# ethernet.net
KiCad netlist of a schematic drawn in Altium Designer
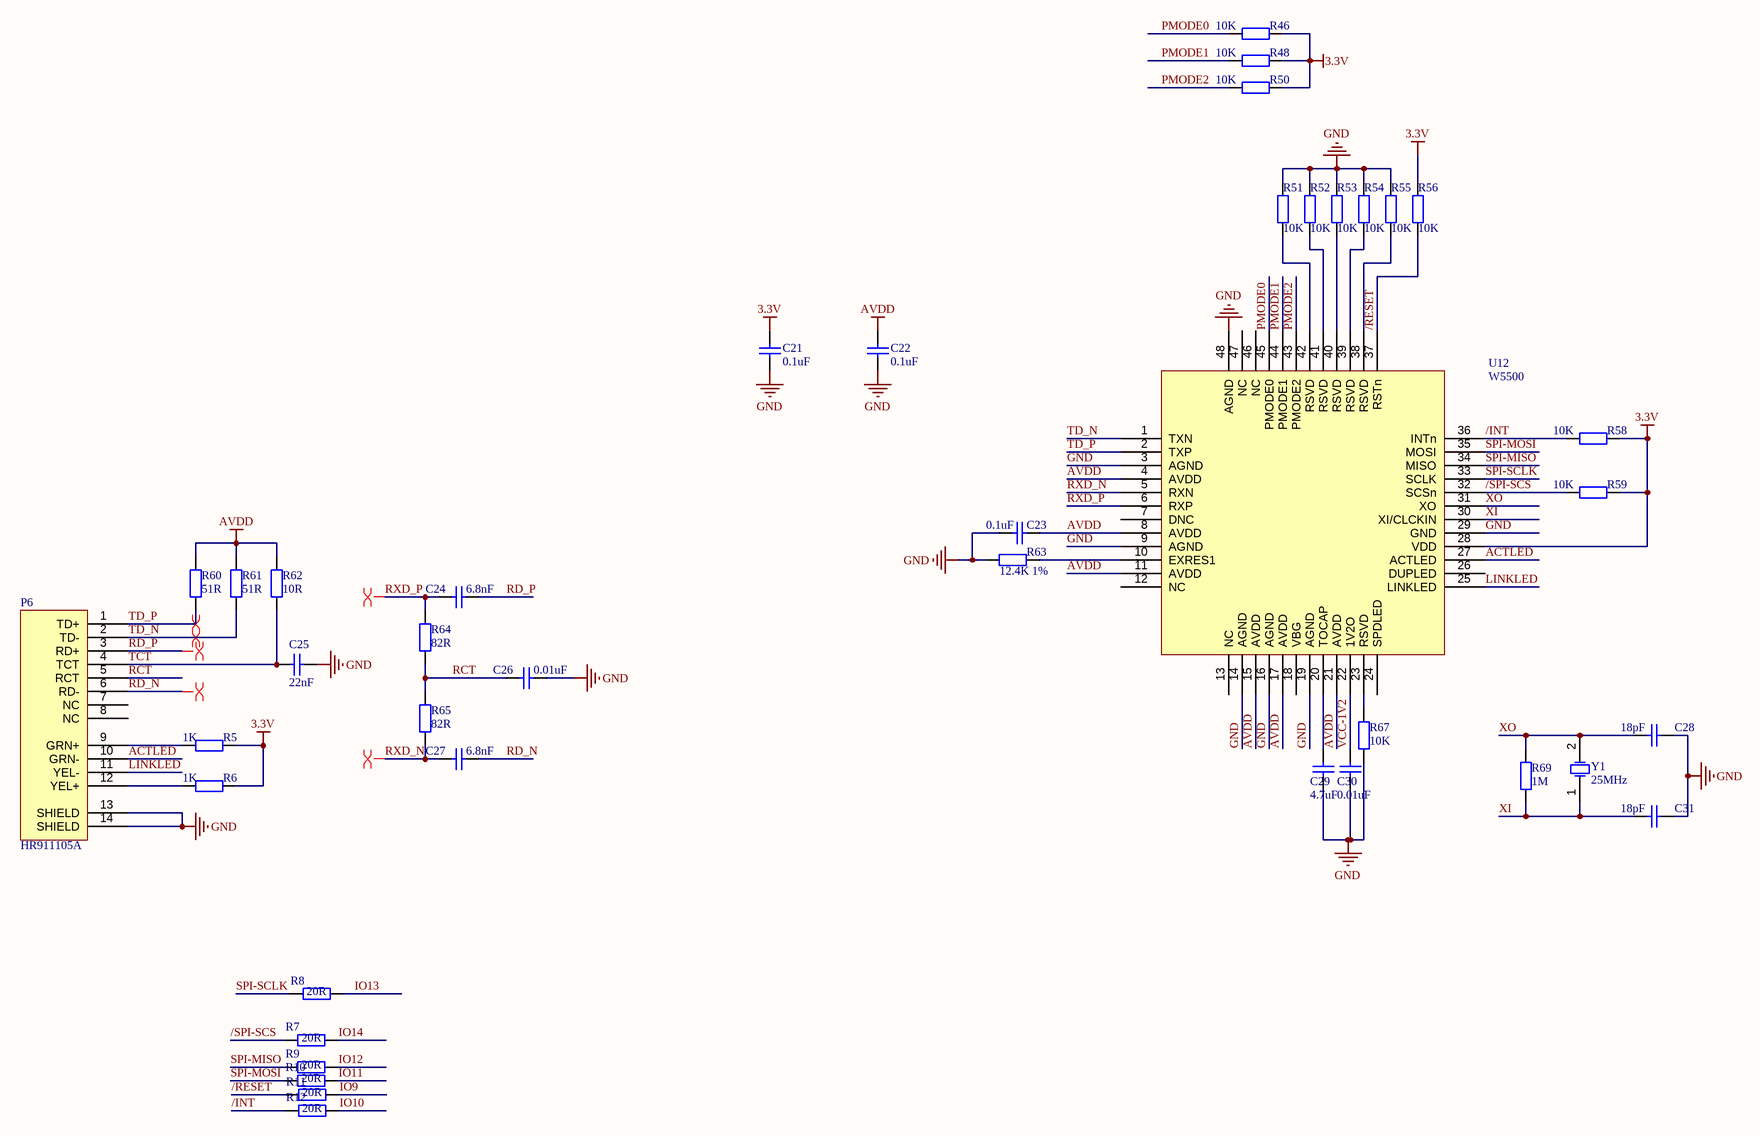
[diagram p0: ethernet.SchDoc]

(export (version "E")
  (design (tool "Eeschema 10.0.6"))
  (components
    (comp (ref "C21")
      (value "0.1uF")
      (footprint "C0805")
      (description "Capacitor")
      (fields (field (name "Comment") "Cap") (field (name "PUBLISHER") "Altium Limited"))
      (libsource (lib "Miscellaneous Devices") (part "Cap"))
    )
    (comp (ref "C22")
      (value "0.1uF")
      (footprint "C0805")
      (description "Capacitor")
      (fields (field (name "Comment") "Cap") (field (name "PUBLISHER") "Altium Limited"))
      (libsource (lib "Miscellaneous Devices") (part "Cap"))
    )
    (comp (ref "C23")
      (value "0.1uF")
      (footprint "C0805")
      (description "Capacitor")
      (fields (field (name "Comment") "Cap") (field (name "PUBLISHER") "Altium Limited"))
      (libsource (lib "Miscellaneous Devices") (part "Cap"))
    )
    (comp (ref "C24")
      (value "6.8nF")
      (footprint "C0805")
      (description "Capacitor")
      (fields (field (name "Comment") "Cap") (field (name "PUBLISHER") "Altium Limited"))
      (libsource (lib "Miscellaneous Devices") (part "Cap"))
    )
    (comp (ref "C25")
      (value "22nF")
      (footprint "C0805")
      (description "Capacitor")
      (fields (field (name "Comment") "Cap") (field (name "PUBLISHER") "Altium Limited"))
      (libsource (lib "Miscellaneous Devices") (part "Cap"))
    )
    (comp (ref "C26")
      (value "0.01uF")
      (footprint "C0805")
      (description "Capacitor")
      (fields (field (name "Comment") "Cap") (field (name "PUBLISHER") "Altium Limited"))
      (libsource (lib "Miscellaneous Devices") (part "Cap"))
    )
    (comp (ref "C27")
      (value "6.8nF")
      (footprint "C0805")
      (description "Capacitor")
      (fields (field (name "Comment") "Cap") (field (name "PUBLISHER") "Altium Limited"))
      (libsource (lib "Miscellaneous Devices") (part "Cap"))
    )
    (comp (ref "C28")
      (value "18pF")
      (footprint "C0805")
      (description "Capacitor")
      (fields (field (name "Comment") "Cap") (field (name "PUBLISHER") "Altium Limited"))
      (libsource (lib "Miscellaneous Devices") (part "Cap"))
    )
    (comp (ref "C29")
      (value "4.7uF")
      (footprint "C0805")
      (description "Capacitor")
      (fields (field (name "Comment") "Cap") (field (name "PUBLISHER") "Altium Limited"))
      (libsource (lib "Miscellaneous Devices") (part "Cap"))
    )
    (comp (ref "C30")
      (value "0.01uF")
      (footprint "C0805")
      (description "Capacitor")
      (fields (field (name "Comment") "Cap") (field (name "PUBLISHER") "Altium Limited"))
      (libsource (lib "Miscellaneous Devices") (part "Cap"))
    )
    (comp (ref "C31")
      (value "18pF")
      (footprint "C0805")
      (description "Capacitor")
      (fields (field (name "Comment") "Cap") (field (name "PUBLISHER") "Altium Limited"))
      (libsource (lib "Miscellaneous Devices") (part "Cap"))
    )
    (comp (ref "P6")
      (value "HR911105A")
      (footprint "HR911105A")
      (description "RJ45插座")
      (libsource (lib "W5500_SCH") (part "HR911105A"))
    )
    (comp (ref "R5")
      (value "1K")
      (footprint "C0805")
      (description "Resistor")
      (fields (field (name "Comment") "Res2") (field (name "PUBLISHER") "Altium Limited"))
      (libsource (lib "") (part "Res2_2"))
    )
    (comp (ref "R6")
      (value "1K")
      (footprint "C0805")
      (description "Resistor")
      (fields (field (name "Comment") "Res2") (field (name "PUBLISHER") "Altium Limited"))
      (libsource (lib "") (part "Res2_2"))
    )
    (comp (ref "R7")
      (value "20R")
      (footprint "C0805")
      (description "Resistor")
      (fields (field (name "Comment") "Res2") (field (name "PUBLISHER") "Altium Limited"))
      (libsource (lib "") (part "Res2_2"))
    )
    (comp (ref "R8")
      (value "20R")
      (footprint "C0805")
      (description "Resistor")
      (fields (field (name "Comment") "Res2") (field (name "PUBLISHER") "Altium Limited"))
      (libsource (lib "") (part "Res2_2"))
    )
    (comp (ref "R9")
      (value "20R")
      (footprint "C0805")
      (description "Resistor")
      (fields (field (name "Comment") "Res2") (field (name "PUBLISHER") "Altium Limited"))
      (libsource (lib "") (part "Res2_2"))
    )
    (comp (ref "R10")
      (value "20R")
      (footprint "C0805")
      (description "Resistor")
      (fields (field (name "Comment") "Res2") (field (name "PUBLISHER") "Altium Limited"))
      (libsource (lib "") (part "Res2_2"))
    )
    (comp (ref "R11")
      (value "20R")
      (footprint "C0805")
      (description "Resistor")
      (fields (field (name "Comment") "Res2") (field (name "PUBLISHER") "Altium Limited"))
      (libsource (lib "") (part "Res2_2"))
    )
    (comp (ref "R12")
      (value "20R")
      (footprint "C0805")
      (description "Resistor")
      (fields (field (name "Comment") "Res2") (field (name "PUBLISHER") "Altium Limited"))
      (libsource (lib "") (part "Res2_2"))
    )
    (comp (ref "R46")
      (value "10K")
      (footprint "C0805")
      (description "Resistor")
      (fields (field (name "Comment") "Res2") (field (name "PUBLISHER") "Altium Limited"))
      (libsource (lib "") (part "Res2_1"))
    )
    (comp (ref "R48")
      (value "10K")
      (footprint "C0805")
      (description "Resistor")
      (fields (field (name "Comment") "Res2") (field (name "PUBLISHER") "Altium Limited"))
      (libsource (lib "") (part "Res2_1"))
    )
    (comp (ref "R50")
      (value "10K")
      (footprint "C0805")
      (description "Resistor")
      (fields (field (name "Comment") "Res2") (field (name "PUBLISHER") "Altium Limited"))
      (libsource (lib "") (part "Res2_1"))
    )
    (comp (ref "R51")
      (value "10K")
      (footprint "C0805")
      (description "Resistor")
      (fields (field (name "Comment") "Res2") (field (name "PUBLISHER") "Altium Limited"))
      (libsource (lib "Miscellaneous Devices") (part "Res2"))
    )
    (comp (ref "R52")
      (value "10K")
      (footprint "C0805")
      (description "Resistor")
      (fields (field (name "Comment") "Res2") (field (name "PUBLISHER") "Altium Limited"))
      (libsource (lib "Miscellaneous Devices") (part "Res2"))
    )
    (comp (ref "R53")
      (value "10K")
      (footprint "C0805")
      (description "Resistor")
      (fields (field (name "Comment") "Res2") (field (name "PUBLISHER") "Altium Limited"))
      (libsource (lib "Miscellaneous Devices") (part "Res2"))
    )
    (comp (ref "R54")
      (value "10K")
      (footprint "C0805")
      (description "Resistor")
      (fields (field (name "Comment") "Res2") (field (name "PUBLISHER") "Altium Limited"))
      (libsource (lib "Miscellaneous Devices") (part "Res2"))
    )
    (comp (ref "R55")
      (value "10K")
      (footprint "C0805")
      (description "Resistor")
      (fields (field (name "Comment") "Res2") (field (name "PUBLISHER") "Altium Limited"))
      (libsource (lib "Miscellaneous Devices") (part "Res2"))
    )
    (comp (ref "R56")
      (value "10K")
      (footprint "C0805")
      (description "Resistor")
      (fields (field (name "Comment") "Res2") (field (name "PUBLISHER") "Altium Limited"))
      (libsource (lib "Miscellaneous Devices") (part "Res2"))
    )
    (comp (ref "R58")
      (value "10K")
      (footprint "C0805")
      (description "Resistor")
      (fields (field (name "Comment") "Res2") (field (name "PUBLISHER") "Altium Limited"))
      (libsource (lib "") (part "Res2_1"))
    )
    (comp (ref "R59")
      (value "10K")
      (footprint "C0805")
      (description "Resistor")
      (fields (field (name "Comment") "Res2") (field (name "PUBLISHER") "Altium Limited"))
      (libsource (lib "") (part "Res2_1"))
    )
    (comp (ref "R60")
      (value "51R")
      (footprint "C0805")
      (description "Resistor")
      (fields (field (name "Comment") "Res2") (field (name "PUBLISHER") "Altium Limited"))
      (libsource (lib "") (part "Res2_3"))
    )
    (comp (ref "R61")
      (value "51R")
      (footprint "C0805")
      (description "Resistor")
      (fields (field (name "Comment") "Res2") (field (name "PUBLISHER") "Altium Limited"))
      (libsource (lib "") (part "Res2_3"))
    )
    (comp (ref "R62")
      (value "10R")
      (footprint "C0805")
      (description "Resistor")
      (fields (field (name "Comment") "Res2") (field (name "PUBLISHER") "Altium Limited"))
      (libsource (lib "") (part "Res2_3"))
    )
    (comp (ref "R63")
      (value "12.4K 1%")
      (footprint "C0805")
      (description "Resistor")
      (fields (field (name "Comment") "Res2") (field (name "PUBLISHER") "Altium Limited"))
      (libsource (lib "") (part "Res2_1"))
    )
    (comp (ref "R64")
      (value "82R")
      (footprint "C0805")
      (description "Resistor")
      (fields (field (name "Comment") "Res2") (field (name "PUBLISHER") "Altium Limited"))
      (libsource (lib "Miscellaneous Devices") (part "Res2"))
    )
    (comp (ref "R65")
      (value "82R")
      (footprint "C0805")
      (description "Resistor")
      (fields (field (name "Comment") "Res2") (field (name "PUBLISHER") "Altium Limited"))
      (libsource (lib "Miscellaneous Devices") (part "Res2"))
    )
    (comp (ref "R67")
      (value "10K")
      (footprint "C0805")
      (description "Resistor")
      (fields (field (name "Comment") "Res2") (field (name "PUBLISHER") "Altium Limited"))
      (libsource (lib "Miscellaneous Devices") (part "Res2"))
    )
    (comp (ref "R69")
      (value "1M")
      (footprint "C0805")
      (description "Resistor")
      (fields (field (name "Comment") "Res2") (field (name "PUBLISHER") "Altium Limited"))
      (libsource (lib "Miscellaneous Devices") (part "Res2"))
    )
    (comp (ref "U12")
      (value "W5500")
      (footprint "LQFP48")
      (description "W5500以太网芯片")
      (libsource (lib "W5500_SCH") (part "W5500"))
    )
    (comp (ref "Y1")
      (value "25MHz")
      (footprint "XTAL-HC49")
      (description "Crystal Oscillator")
      (fields (field (name "PUBLISHER") "Altium Limited"))
      (libsource (lib "Miscellaneous Devices") (part "XTAL"))
    )
  )
  (nets
    (net (code "1") (name "/ACTLED") (class "Default")
      (node (ref "P6") (pin "10") (pinfunction "GRN-_10") (pintype "passive"))
      (node (ref "U12") (pin "27") (pinfunction "ACTLED_27") (pintype "passive"))
    )
    (net (code "2") (name "/IO9") (class "Default")
      (node (ref "R11") (pin "1") (pinfunction "1_1") (pintype "passive"))
    )
    (net (code "3") (name "/IO10") (class "Default")
      (node (ref "R12") (pin "1") (pinfunction "1_1") (pintype "passive"))
    )
    (net (code "4") (name "/IO11") (class "Default")
      (node (ref "R10") (pin "1") (pinfunction "1_1") (pintype "passive"))
    )
    (net (code "5") (name "/IO12") (class "Default")
      (node (ref "R9") (pin "1") (pinfunction "1_1") (pintype "passive"))
    )
    (net (code "6") (name "/IO13") (class "Default")
      (node (ref "R8") (pin "1") (pinfunction "1_1") (pintype "passive"))
    )
    (net (code "7") (name "/IO14") (class "Default")
      (node (ref "R7") (pin "1") (pinfunction "1_1") (pintype "passive"))
    )
    (net (code "8") (name "/LINKLED") (class "Default")
      (node (ref "P6") (pin "11") (pinfunction "YEL-_11") (pintype "passive"))
      (node (ref "U12") (pin "25") (pinfunction "LINKLED_25") (pintype "passive"))
    )
    (net (code "9") (name "/PMODE0") (class "Default")
      (node (ref "R46") (pin "1") (pinfunction "1_1") (pintype "passive"))
      (node (ref "U12") (pin "45") (pinfunction "PMODE0_45") (pintype "passive"))
    )
    (net (code "10") (name "/PMODE1") (class "Default")
      (node (ref "R48") (pin "1") (pinfunction "1_1") (pintype "passive"))
      (node (ref "U12") (pin "44") (pinfunction "PMODE1_44") (pintype "passive"))
    )
    (net (code "11") (name "/PMODE2") (class "Default")
      (node (ref "R50") (pin "1") (pinfunction "1_1") (pintype "passive"))
      (node (ref "U12") (pin "43") (pinfunction "PMODE2_43") (pintype "passive"))
    )
    (net (code "12") (name "/RCT") (class "Default")
      (node (ref "C26") (pin "2") (pinfunction "2_2") (pintype "passive"))
      (node (ref "P6") (pin "5") (pinfunction "RCT_5") (pintype "passive"))
      (node (ref "R64") (pin "1") (pinfunction "1_1") (pintype "passive"))
      (node (ref "R65") (pin "2") (pinfunction "2_2") (pintype "passive"))
    )
    (net (code "13") (name "/RD_N") (class "Default")
      (node (ref "C27") (pin "1") (pinfunction "1_1") (pintype "passive"))
      (node (ref "P6") (pin "6") (pinfunction "RD-_6") (pintype "passive"))
    )
    (net (code "14") (name "/RD_P") (class "Default")
      (node (ref "C24") (pin "1") (pinfunction "1_1") (pintype "passive"))
      (node (ref "P6") (pin "3") (pinfunction "RD+_3") (pintype "passive"))
    )
    (net (code "15") (name "/RXD_N") (class "Default")
      (node (ref "C27") (pin "2") (pinfunction "2_2") (pintype "passive"))
      (node (ref "R65") (pin "1") (pinfunction "1_1") (pintype "passive"))
      (node (ref "U12") (pin "5") (pinfunction "RXN_5") (pintype "passive"))
    )
    (net (code "16") (name "/RXD_P") (class "Default")
      (node (ref "C24") (pin "2") (pinfunction "2_2") (pintype "passive"))
      (node (ref "R64") (pin "2") (pinfunction "2_2") (pintype "passive"))
      (node (ref "U12") (pin "6") (pinfunction "RXP_6") (pintype "passive"))
    )
    (net (code "17") (name "/SPI-MISO") (class "Default")
      (node (ref "R9") (pin "2") (pinfunction "2_2") (pintype "passive"))
      (node (ref "U12") (pin "34") (pinfunction "MISO_34") (pintype "passive"))
    )
    (net (code "18") (name "/SPI-MOSI") (class "Default")
      (node (ref "R10") (pin "2") (pinfunction "2_2") (pintype "passive"))
      (node (ref "U12") (pin "35") (pinfunction "MOSI_35") (pintype "passive"))
    )
    (net (code "19") (name "/SPI-SCLK") (class "Default")
      (node (ref "R8") (pin "2") (pinfunction "2_2") (pintype "passive"))
      (node (ref "U12") (pin "33") (pinfunction "SCLK_33") (pintype "passive"))
    )
    (net (code "20") (name "/TCT") (class "Default")
      (node (ref "C25") (pin "1") (pinfunction "1_1") (pintype "passive"))
      (node (ref "P6") (pin "4") (pinfunction "TCT_4") (pintype "passive"))
      (node (ref "R62") (pin "2") (pinfunction "2_2") (pintype "passive"))
    )
    (net (code "21") (name "/TD_N") (class "Default")
      (node (ref "P6") (pin "2") (pinfunction "TD-_2") (pintype "passive"))
      (node (ref "R61") (pin "2") (pinfunction "2_2") (pintype "passive"))
      (node (ref "U12") (pin "1") (pinfunction "TXN_1") (pintype "passive"))
    )
    (net (code "22") (name "/TD_P") (class "Default")
      (node (ref "P6") (pin "1") (pinfunction "TD+_1") (pintype "passive"))
      (node (ref "R60") (pin "2") (pinfunction "2_2") (pintype "passive"))
      (node (ref "U12") (pin "2") (pinfunction "TXP_2") (pintype "passive"))
    )
    (net (code "23") (name "/VCC-1V2") (class "Default")
      (node (ref "C30") (pin "1") (pinfunction "1_1") (pintype "passive"))
      (node (ref "U12") (pin "22") (pinfunction "1V2O_22") (pintype "passive"))
    )
    (net (code "24") (name "/XI") (class "Default")
      (node (ref "C31") (pin "2") (pinfunction "2_2") (pintype "passive"))
      (node (ref "R69") (pin "1") (pinfunction "1_1") (pintype "passive"))
      (node (ref "U12") (pin "30") (pinfunction "XI/CLCKIN_30") (pintype "passive"))
      (node (ref "Y1") (pin "1") (pinfunction "OSC1_1") (pintype "passive"))
    )
    (net (code "25") (name "/XO") (class "Default")
      (node (ref "C28") (pin "2") (pinfunction "2_2") (pintype "passive"))
      (node (ref "R69") (pin "2") (pinfunction "2_2") (pintype "passive"))
      (node (ref "U12") (pin "31") (pinfunction "XO_31") (pintype "passive"))
      (node (ref "Y1") (pin "2") (pinfunction "OSC2_2") (pintype "passive"))
    )
    (net (code "26") (name "/{slash}INT") (class "Default")
      (node (ref "R12") (pin "2") (pinfunction "2_2") (pintype "passive"))
      (node (ref "R58") (pin "1") (pinfunction "1_1") (pintype "passive"))
      (node (ref "U12") (pin "36") (pinfunction "INTn_36") (pintype "passive"))
    )
    (net (code "27") (name "/{slash}RESET") (class "Default")
      (node (ref "R11") (pin "2") (pinfunction "2_2") (pintype "passive"))
      (node (ref "R56") (pin "1") (pinfunction "1_1") (pintype "passive"))
      (node (ref "U12") (pin "37") (pinfunction "RSTn_37") (pintype "passive"))
    )
    (net (code "28") (name "/{slash}SPI-SCS") (class "Default")
      (node (ref "R59") (pin "1") (pinfunction "1_1") (pintype "passive"))
      (node (ref "R7") (pin "2") (pinfunction "2_2") (pintype "passive"))
      (node (ref "U12") (pin "32") (pinfunction "SCSn_32") (pintype "passive"))
    )
    (net (code "29") (name "3.3V") (class "Default")
      (node (ref "C21") (pin "1") (pinfunction "1_1") (pintype "passive"))
      (node (ref "R46") (pin "2") (pinfunction "2_2") (pintype "passive"))
      (node (ref "R48") (pin "2") (pinfunction "2_2") (pintype "passive"))
      (node (ref "R5") (pin "1") (pinfunction "1_1") (pintype "passive"))
      (node (ref "R50") (pin "2") (pinfunction "2_2") (pintype "passive"))
      (node (ref "R56") (pin "2") (pinfunction "2_2") (pintype "passive"))
      (node (ref "R58") (pin "2") (pinfunction "2_2") (pintype "passive"))
      (node (ref "R59") (pin "2") (pinfunction "2_2") (pintype "passive"))
      (node (ref "R6") (pin "1") (pinfunction "1_1") (pintype "passive"))
      (node (ref "U12") (pin "28") (pinfunction "VDD_28") (pintype "passive"))
    )
    (net (code "30") (name "AVDD") (class "Default")
      (node (ref "C22") (pin "2") (pinfunction "2_2") (pintype "passive"))
      (node (ref "C23") (pin "1") (pinfunction "1_1") (pintype "passive"))
      (node (ref "R60") (pin "1") (pinfunction "1_1") (pintype "passive"))
      (node (ref "R61") (pin "1") (pinfunction "1_1") (pintype "passive"))
      (node (ref "R62") (pin "1") (pinfunction "1_1") (pintype "passive"))
      (node (ref "U12") (pin "11") (pinfunction "AVDD_11") (pintype "passive"))
      (node (ref "U12") (pin "15") (pinfunction "AVDD_15") (pintype "passive"))
      (node (ref "U12") (pin "17") (pinfunction "AVDD_17") (pintype "passive"))
      (node (ref "U12") (pin "21") (pinfunction "AVDD_21") (pintype "passive"))
      (node (ref "U12") (pin "4") (pinfunction "AVDD_4") (pintype "passive"))
      (node (ref "U12") (pin "8") (pinfunction "AVDD_8") (pintype "passive"))
    )
    (net (code "31") (name "GND") (class "Default")
      (node (ref "C21") (pin "2") (pinfunction "2_2") (pintype "passive"))
      (node (ref "C22") (pin "1") (pinfunction "1_1") (pintype "passive"))
      (node (ref "C23") (pin "2") (pinfunction "2_2") (pintype "passive"))
      (node (ref "C25") (pin "2") (pinfunction "2_2") (pintype "passive"))
      (node (ref "C26") (pin "1") (pinfunction "1_1") (pintype "passive"))
      (node (ref "C28") (pin "1") (pinfunction "1_1") (pintype "passive"))
      (node (ref "C29") (pin "2") (pinfunction "2_2") (pintype "passive"))
      (node (ref "C30") (pin "2") (pinfunction "2_2") (pintype "passive"))
      (node (ref "C31") (pin "1") (pinfunction "1_1") (pintype "passive"))
      (node (ref "P6") (pin "13") (pinfunction "SHIELD_13") (pintype "passive"))
      (node (ref "P6") (pin "14") (pinfunction "SHIELD_14") (pintype "passive"))
      (node (ref "R51") (pin "2") (pinfunction "2_2") (pintype "passive"))
      (node (ref "R52") (pin "2") (pinfunction "2_2") (pintype "passive"))
      (node (ref "R53") (pin "2") (pinfunction "2_2") (pintype "passive"))
      (node (ref "R54") (pin "2") (pinfunction "2_2") (pintype "passive"))
      (node (ref "R55") (pin "2") (pinfunction "2_2") (pintype "passive"))
      (node (ref "R63") (pin "1") (pinfunction "1_1") (pintype "passive"))
      (node (ref "R67") (pin "1") (pinfunction "1_1") (pintype "passive"))
      (node (ref "U12") (pin "14") (pinfunction "AGND_14") (pintype "passive"))
      (node (ref "U12") (pin "16") (pinfunction "AGND_16") (pintype "passive"))
      (node (ref "U12") (pin "19") (pinfunction "AGND_19") (pintype "passive"))
      (node (ref "U12") (pin "29") (pinfunction "GND_29") (pintype "passive"))
      (node (ref "U12") (pin "3") (pinfunction "AGND_3") (pintype "passive"))
      (node (ref "U12") (pin "48") (pinfunction "AGND_48") (pintype "passive"))
      (node (ref "U12") (pin "9") (pinfunction "AGND_9") (pintype "passive"))
    )
    (net (code "32") (name "Net-(P6-GRN+)") (class "Default")
      (node (ref "P6") (pin "9") (pinfunction "GRN+_9") (pintype "passive"))
      (node (ref "R5") (pin "2") (pinfunction "2_2") (pintype "passive"))
    )
    (net (code "33") (name "Net-(P6-YEL+)") (class "Default")
      (node (ref "P6") (pin "12") (pinfunction "YEL+_12") (pintype "passive"))
      (node (ref "R6") (pin "2") (pinfunction "2_2") (pintype "passive"))
    )
    (net (code "34") (name "Net-(R51-Pad1)") (class "Default")
      (node (ref "R51") (pin "1") (pinfunction "1_1") (pintype "passive"))
      (node (ref "U12") (pin "42") (pinfunction "RSVD_42") (pintype "passive"))
    )
    (net (code "35") (name "Net-(R52-Pad1)") (class "Default")
      (node (ref "R52") (pin "1") (pinfunction "1_1") (pintype "passive"))
      (node (ref "U12") (pin "41") (pinfunction "RSVD_41") (pintype "passive"))
    )
    (net (code "36") (name "Net-(R53-Pad1)") (class "Default")
      (node (ref "R53") (pin "1") (pinfunction "1_1") (pintype "passive"))
      (node (ref "U12") (pin "40") (pinfunction "RSVD_40") (pintype "passive"))
    )
    (net (code "37") (name "Net-(R54-Pad1)") (class "Default")
      (node (ref "R54") (pin "1") (pinfunction "1_1") (pintype "passive"))
      (node (ref "U12") (pin "39") (pinfunction "RSVD_39") (pintype "passive"))
    )
    (net (code "38") (name "Net-(R55-Pad1)") (class "Default")
      (node (ref "R55") (pin "1") (pinfunction "1_1") (pintype "passive"))
      (node (ref "U12") (pin "38") (pinfunction "RSVD_38") (pintype "passive"))
    )
    (net (code "39") (name "Net-(R67-Pad2)") (class "Default")
      (node (ref "R67") (pin "2") (pinfunction "2_2") (pintype "passive"))
      (node (ref "U12") (pin "23") (pinfunction "RSVD_23") (pintype "passive"))
    )
    (net (code "40") (name "Net-(U12-EXRES1)") (class "Default")
      (node (ref "R63") (pin "2") (pinfunction "2_2") (pintype "passive"))
      (node (ref "U12") (pin "10") (pinfunction "EXRES1_10") (pintype "passive"))
    )
    (net (code "41") (name "Net-(U12-TOCAP)") (class "Default")
      (node (ref "C29") (pin "1") (pinfunction "1_1") (pintype "passive"))
      (node (ref "U12") (pin "20") (pinfunction "TOCAP_20") (pintype "passive"))
    )
    (net (code "42") (name "unconnected-(P6-NC-Pad7)") (class "Default")
      (node (ref "P6") (pin "7") (pinfunction "NC_7") (pintype "passive"))
    )
    (net (code "43") (name "unconnected-(P6-NC-Pad8)") (class "Default")
      (node (ref "P6") (pin "8") (pinfunction "NC_8") (pintype "passive"))
    )
    (net (code "44") (name "unconnected-(U12-DNC-Pad7)") (class "Default")
      (node (ref "U12") (pin "7") (pinfunction "DNC_7") (pintype "passive"))
    )
    (net (code "45") (name "unconnected-(U12-DUPLED-Pad26)") (class "Default")
      (node (ref "U12") (pin "26") (pinfunction "DUPLED_26") (pintype "passive"))
    )
    (net (code "46") (name "unconnected-(U12-NC-Pad12)") (class "Default")
      (node (ref "U12") (pin "12") (pinfunction "NC_12") (pintype "passive"))
    )
    (net (code "47") (name "unconnected-(U12-NC-Pad13)") (class "Default")
      (node (ref "U12") (pin "13") (pinfunction "NC_13") (pintype "passive"))
    )
    (net (code "48") (name "unconnected-(U12-NC-Pad46)") (class "Default")
      (node (ref "U12") (pin "46") (pinfunction "NC_46") (pintype "passive"))
    )
    (net (code "49") (name "unconnected-(U12-NC-Pad47)") (class "Default")
      (node (ref "U12") (pin "47") (pinfunction "NC_47") (pintype "passive"))
    )
    (net (code "50") (name "unconnected-(U12-SPDLED-Pad24)") (class "Default")
      (node (ref "U12") (pin "24") (pinfunction "SPDLED_24") (pintype "passive"))
    )
    (net (code "51") (name "unconnected-(U12-VBG-Pad18)") (class "Default")
      (node (ref "U12") (pin "18") (pinfunction "VBG_18") (pintype "passive"))
    )
  )
)
